# -X_panel_FM_2U_Ver1_v1.net
KiCad netlist of a schematic drawn in EAGLE
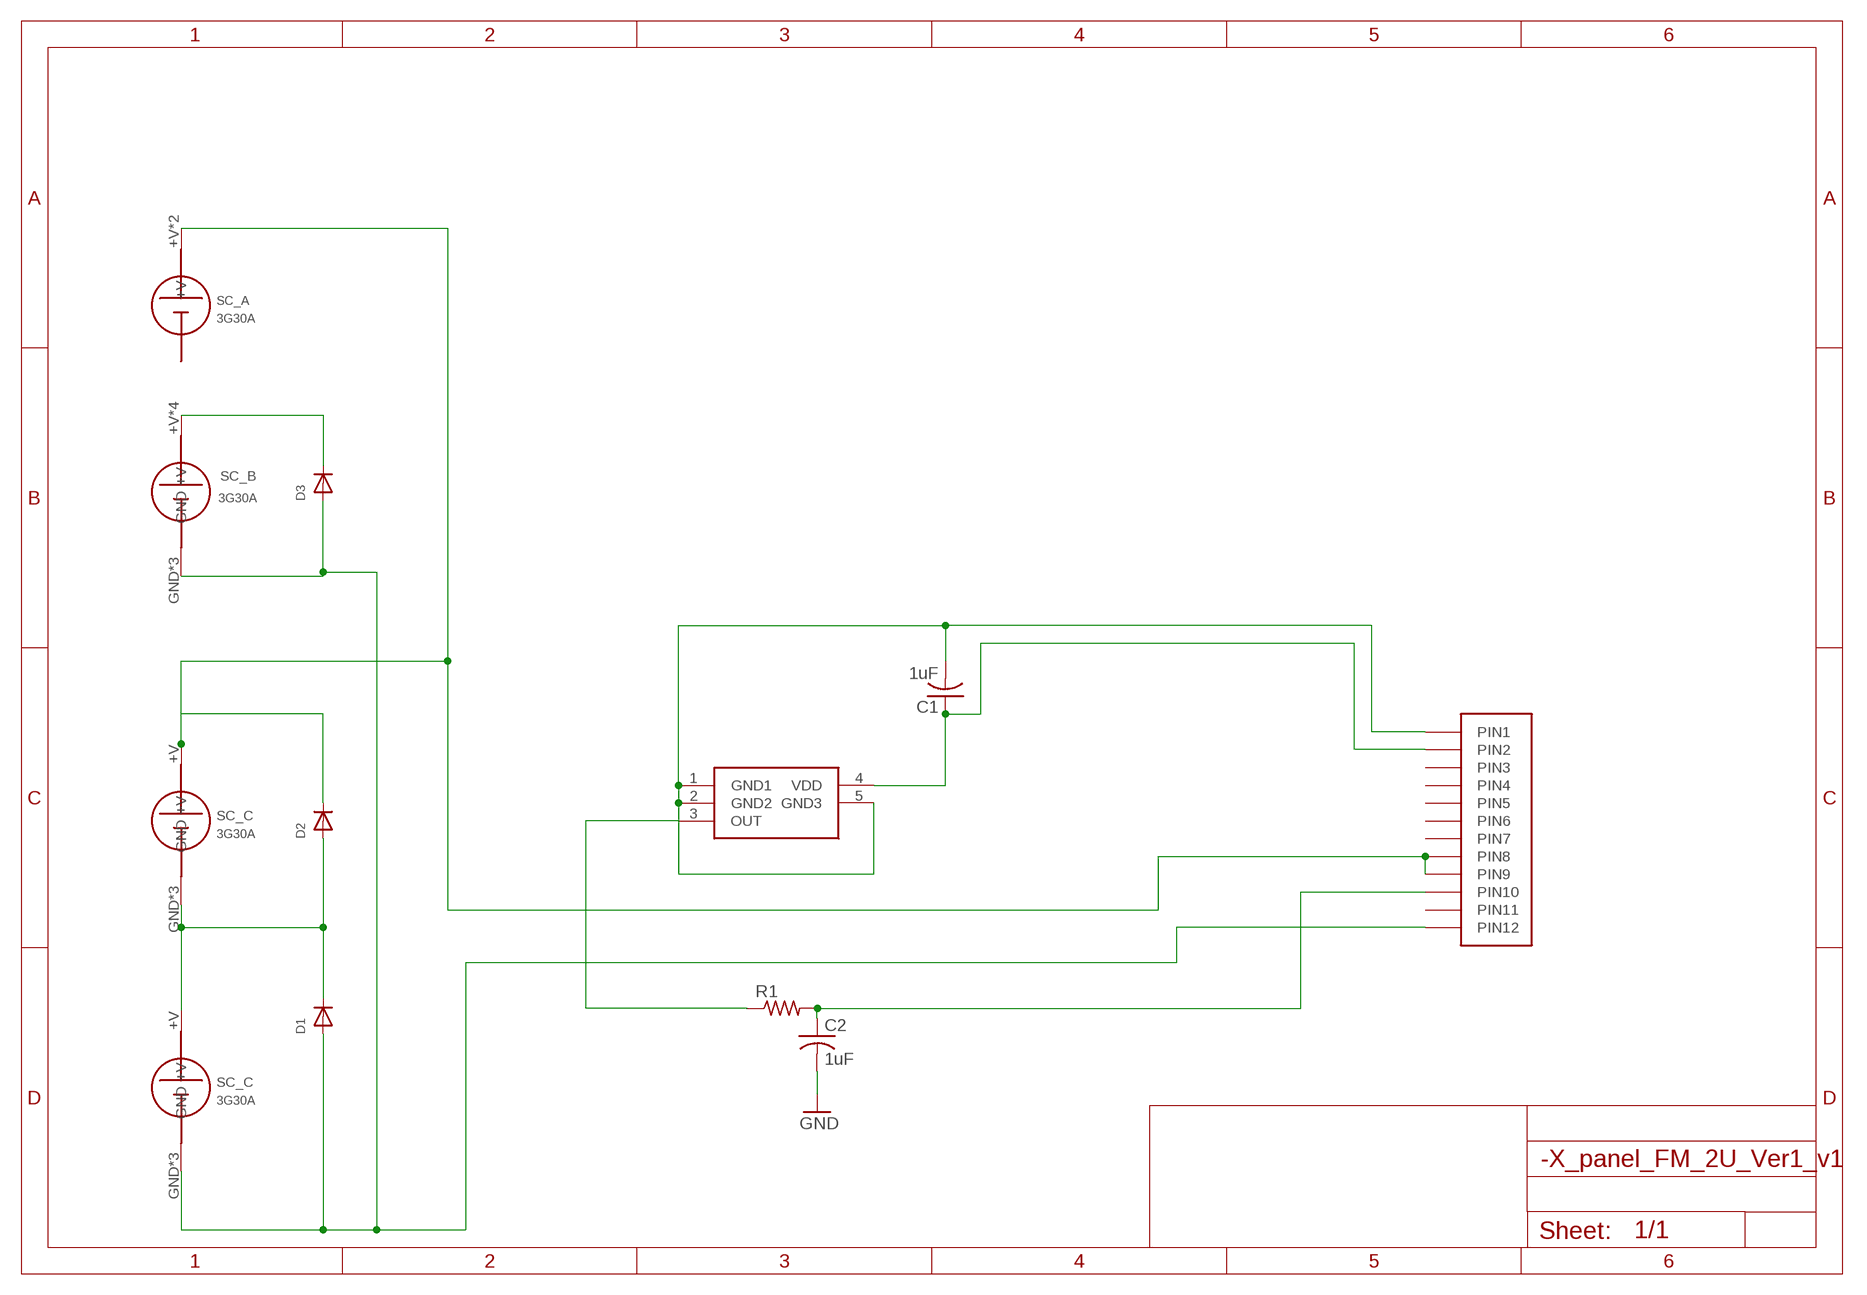
[diagram p0: schematic, sheet 1]

(export (version "E")
  (design (tool "Eeschema 10.0.6"))
  (components
    (comp (ref "C1")
      (value "1uF")
      (footprint "eagle-import:C0805")
      (libsource (lib "eagle-import") (part "C-USC0805"))
    )
    (comp (ref "C2")
      (value "1uF")
      (footprint "eagle-import:C0805")
      (libsource (lib "eagle-import") (part "C-USC0805"))
    )
    (comp (ref "D1")
      (value "DIODE_SOD-123FL")
      (footprint "eagle-import:SOD-123FL")
      (libsource (lib "eagle-import") (part "DIODE_SOD-123FL"))
    )
    (comp (ref "D2")
      (value "DIODE_SOD-123FL")
      (footprint "eagle-import:SOD-123FL")
      (libsource (lib "eagle-import") (part "DIODE_SOD-123FL"))
    )
    (comp (ref "D3")
      (value "DIODE_SOD-123FL")
      (footprint "eagle-import:SOD-123FL")
      (libsource (lib "eagle-import") (part "DIODE_SOD-123FL"))
    )
    (comp (ref "R1")
      (value "R-US_R0402")
      (footprint "eagle-import:R0402")
      (libsource (lib "eagle-import") (part "R-US_R0402"))
    )
    (comp (ref "SOLARCELL_A")
      (value "SC_A")
      (footprint "eagle-import:SC_A")
      (libsource (lib "eagle-import") (part "SC_A"))
    )
    (comp (ref "SOLARCELL_B")
      (value "SC_B")
      (footprint "eagle-import:SC_B")
      (libsource (lib "eagle-import") (part "SC_B"))
    )
    (comp (ref "U$1")
      (value "HEADER12PIN")
      (footprint "eagle-import:HEADER12PIN")
      (libsource (lib "eagle-import") (part "HEADER12PIN"))
    )
    (comp (ref "U$3")
      (value "LMT84DCKT")
      (footprint "eagle-import:SOT65P210X110-5N")
      (fields (field (name "RS_PART_NUMBER") "8115860"))
      (libsource (lib "eagle-import") (part "LMT84DCKT"))
    )
    (comp (ref "U$4")
      (value "SC_C")
      (footprint "eagle-import:SC_C")
      (libsource (lib "eagle-import") (part "SC_C"))
    )
    (comp (ref "U$5")
      (value "SC_C")
      (footprint "eagle-import:SC_C")
      (libsource (lib "eagle-import") (part "SC_C"))
    )
  )
  (nets
    (net (code "1") (name "GND") (class "Default")
      (node (ref "C1") (pin "2") (pinfunction "2_2") (pintype "passive"))
      (node (ref "C2") (pin "2") (pinfunction "2_2") (pintype "passive"))
      (node (ref "D1") (pin "A") (pinfunction "A_A") (pintype "passive"))
      (node (ref "D3") (pin "A") (pinfunction "A_A") (pintype "passive"))
      (node (ref "SOLARCELL_B") (pin "GND") (pinfunction "GND_GND") (pintype "bidirectional"))
      (node (ref "SOLARCELL_B") (pin "GND1") (pinfunction "GND_GND1") (pintype "bidirectional"))
      (node (ref "SOLARCELL_B") (pin "GND2") (pinfunction "GND_GND2") (pintype "bidirectional"))
      (node (ref "U$1") (pin "P1") (pinfunction "PIN1_P1") (pintype "bidirectional"))
      (node (ref "U$1") (pin "P12") (pinfunction "PIN12_P12") (pintype "bidirectional"))
      (node (ref "U$3") (pin "1") (pinfunction "GND1_1") (pintype "power_in"))
      (node (ref "U$3") (pin "2") (pinfunction "GND2_2") (pintype "power_in"))
      (node (ref "U$3") (pin "5") (pinfunction "GND3_5") (pintype "power_in"))
      (node (ref "U$5") (pin "GND") (pinfunction "GND_GND") (pintype "bidirectional"))
      (node (ref "U$5") (pin "GND1") (pinfunction "GND_GND1") (pintype "bidirectional"))
      (node (ref "U$5") (pin "GND2") (pinfunction "GND_GND2") (pintype "bidirectional"))
    )
    (net (code "2") (name "Net-(D1-PadC)") (class "Default")
      (node (ref "D1") (pin "C") (pinfunction "C_C") (pintype "passive"))
      (node (ref "D2") (pin "A") (pinfunction "A_A") (pintype "passive"))
      (node (ref "U$4") (pin "GND") (pinfunction "GND_GND") (pintype "bidirectional"))
      (node (ref "U$4") (pin "GND1") (pinfunction "GND_GND1") (pintype "bidirectional"))
      (node (ref "U$4") (pin "GND2") (pinfunction "GND_GND2") (pintype "bidirectional"))
      (node (ref "U$5") (pin "+V") (pinfunction "+V_+V") (pintype "bidirectional"))
    )
    (net (code "3") (name "Net-(D3-PadC)") (class "Default")
      (node (ref "D3") (pin "C") (pinfunction "C_C") (pintype "passive"))
      (node (ref "SOLARCELL_B") (pin "+V") (pinfunction "+V_+V") (pintype "bidirectional"))
      (node (ref "SOLARCELL_B") (pin "+V2") (pinfunction "+V_+V2") (pintype "bidirectional"))
      (node (ref "SOLARCELL_B") (pin "+V3") (pinfunction "+V_+V3") (pintype "bidirectional"))
      (node (ref "SOLARCELL_B") (pin "+V4") (pinfunction "+V_+V4") (pintype "bidirectional"))
    )
    (net (code "4") (name "Net-(U$1-PIN2)") (class "Default")
      (node (ref "C1") (pin "1") (pinfunction "1_1") (pintype "passive"))
      (node (ref "U$1") (pin "P2") (pinfunction "PIN2_P2") (pintype "bidirectional"))
      (node (ref "U$3") (pin "4") (pinfunction "VDD_4") (pintype "power_in"))
    )
    (net (code "5") (name "Net-(U$1-PIN8)") (class "Default")
      (node (ref "D2") (pin "C") (pinfunction "C_C") (pintype "passive"))
      (node (ref "SOLARCELL_A") (pin "+V") (pinfunction "+V_+V") (pintype "bidirectional"))
      (node (ref "SOLARCELL_A") (pin "+V1") (pinfunction "+V_+V1") (pintype "bidirectional"))
      (node (ref "U$1") (pin "P8") (pinfunction "PIN8_P8") (pintype "bidirectional"))
      (node (ref "U$1") (pin "P9") (pinfunction "PIN9_P9") (pintype "bidirectional"))
      (node (ref "U$4") (pin "+V") (pinfunction "+V_+V") (pintype "bidirectional"))
    )
    (net (code "6") (name "Net-(U$1-PIN10)") (class "Default")
      (node (ref "C2") (pin "1") (pinfunction "1_1") (pintype "passive"))
      (node (ref "R1") (pin "2") (pinfunction "2_2") (pintype "passive"))
      (node (ref "U$1") (pin "P10") (pinfunction "PIN10_P10") (pintype "bidirectional"))
    )
    (net (code "7") (name "Net-(U$3-OUT)") (class "Default")
      (node (ref "R1") (pin "1") (pinfunction "1_1") (pintype "passive"))
      (node (ref "U$3") (pin "3") (pinfunction "OUT_3") (pintype "output"))
    )
    (net (code "8") (name "unconnected-(U$1-PIN3-PadP3)") (class "Default")
      (node (ref "U$1") (pin "P3") (pinfunction "PIN3_P3") (pintype "bidirectional"))
    )
    (net (code "9") (name "unconnected-(U$1-PIN4-PadP4)") (class "Default")
      (node (ref "U$1") (pin "P4") (pinfunction "PIN4_P4") (pintype "bidirectional"))
    )
    (net (code "10") (name "unconnected-(U$1-PIN5-PadP5)") (class "Default")
      (node (ref "U$1") (pin "P5") (pinfunction "PIN5_P5") (pintype "bidirectional"))
    )
    (net (code "11") (name "unconnected-(U$1-PIN6-PadP6)") (class "Default")
      (node (ref "U$1") (pin "P6") (pinfunction "PIN6_P6") (pintype "bidirectional"))
    )
    (net (code "12") (name "unconnected-(U$1-PIN7-PadP7)") (class "Default")
      (node (ref "U$1") (pin "P7") (pinfunction "PIN7_P7") (pintype "bidirectional"))
    )
    (net (code "13") (name "unconnected-(U$1-PIN11-PadP11)") (class "Default")
      (node (ref "U$1") (pin "P11") (pinfunction "PIN11_P11") (pintype "bidirectional"))
    )
  )
)
